# 0000.net
KiCad netlist of a schematic drawn in EasyEDA
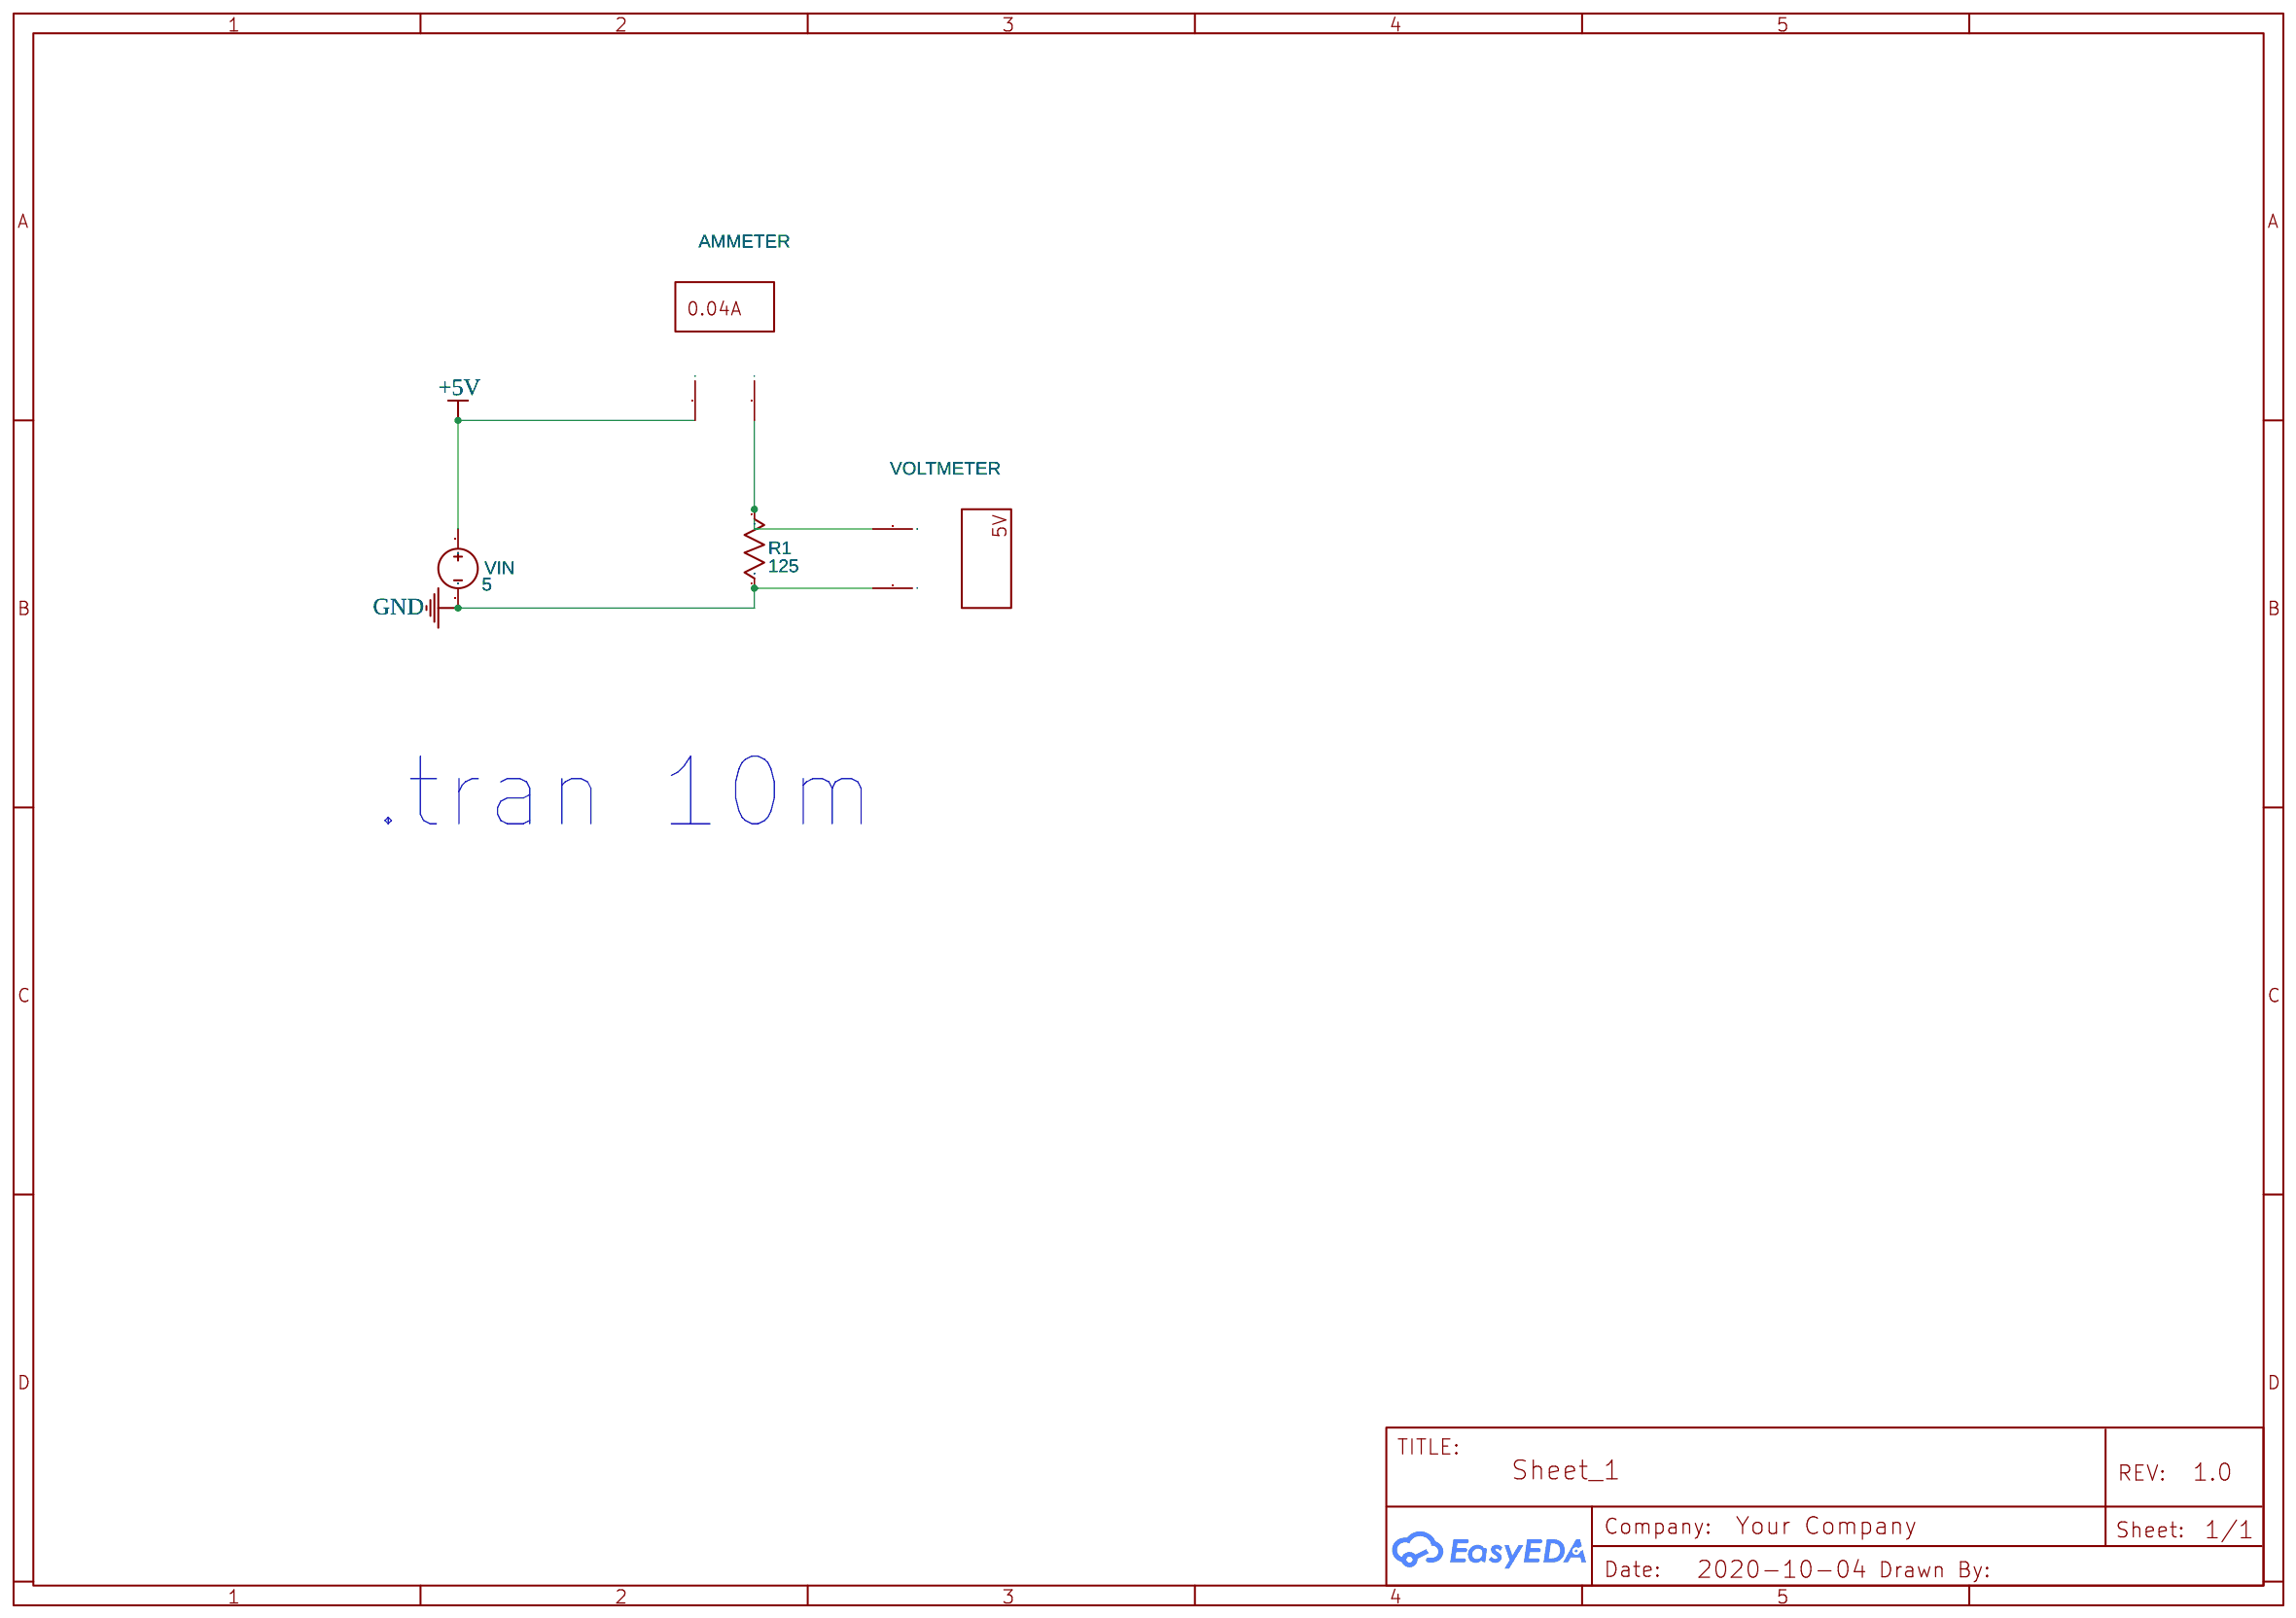
[diagram p0: schematic sheet]

(export (version "E")
  (design (tool "Eeschema 10.0.6"))
  (components
    (comp (ref "AMMETER") (value "Multimeter") (libsource (lib "") (part "MULTIMETER")))
    (comp (ref "R1") (value "125") (libsource (lib "") (part "Resistor_US")))
    (comp (ref "VIN") (value "5") (libsource (lib "") (part "VDC")))
    (comp (ref "VOLTMETER") (value "Multimeter") (libsource (lib "") (part "MULTIMETER_1")))
  )
  (nets
    (net (code "1") (name "+5V") (class "Default")
      (node (ref "AMMETER") (pin "1") (pinfunction "+_1") (pintype "unspecified"))
      (node (ref "VIN") (pin "1") (pinfunction "1_1") (pintype "unspecified"))
    )
    (net (code "2") (name "GND") (class "Default")
      (node (ref "R1") (pin "1") (pinfunction "1_1") (pintype "unspecified"))
      (node (ref "VIN") (pin "2") (pinfunction "2_2") (pintype "unspecified"))
      (node (ref "VOLTMETER") (pin "2") (pinfunction "I_2") (pintype "unspecified"))
    )
    (net (code "3") (name "Net-(AMMETER-I)") (class "Default")
      (node (ref "AMMETER") (pin "2") (pinfunction "I_2") (pintype "unspecified"))
      (node (ref "R1") (pin "2") (pinfunction "2_2") (pintype "unspecified"))
      (node (ref "VOLTMETER") (pin "1") (pinfunction "+_1") (pintype "unspecified"))
    )
  )
)
